# currentSense.net
KiCad netlist of a schematic drawn in Altium Designer
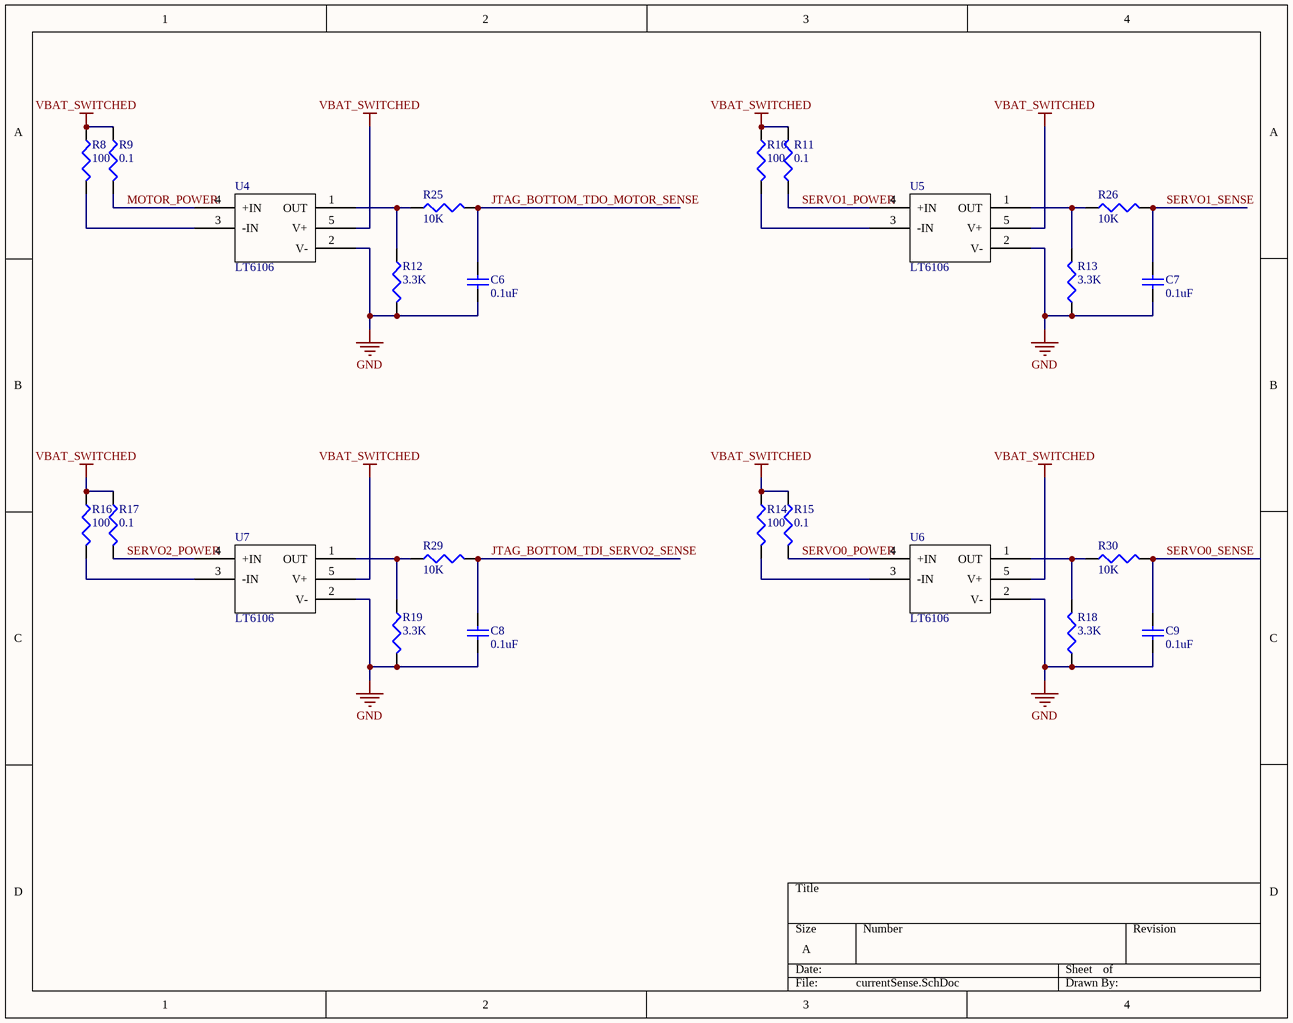
[diagram p0: currentSense.SchDoc]

(export (version "E")
  (design (tool "Eeschema 10.0.6"))
  (components
    (comp (ref "C6")
      (value "0.1uF")
      (footprint "CAPC1005L")
      (description "Capacitor (Semiconductor SIM Model)")
      (fields (field (name "Comment") "Cap Semi") (field (name "PUBLISHER") "Altium Limited"))
      (libsource (lib "Miscellaneous Devices") (part "Cap Semi"))
    )
    (comp (ref "C7")
      (value "0.1uF")
      (footprint "CAPC1005L")
      (description "Capacitor (Semiconductor SIM Model)")
      (fields (field (name "Comment") "Cap Semi") (field (name "PUBLISHER") "Altium Limited"))
      (libsource (lib "Miscellaneous Devices") (part "Cap Semi"))
    )
    (comp (ref "C8")
      (value "0.1uF")
      (footprint "CAPC1005L")
      (description "Capacitor (Semiconductor SIM Model)")
      (fields (field (name "Comment") "Cap Semi") (field (name "PUBLISHER") "Altium Limited"))
      (libsource (lib "Miscellaneous Devices") (part "Cap Semi"))
    )
    (comp (ref "C9")
      (value "0.1uF")
      (footprint "CAPC1005L")
      (description "Capacitor (Semiconductor SIM Model)")
      (fields (field (name "Comment") "Cap Semi") (field (name "PUBLISHER") "Altium Limited"))
      (libsource (lib "Miscellaneous Devices") (part "Cap Semi"))
    )
    (comp (ref "R8")
      (value "100")
      (footprint "J1-0603")
      (description "Resistor")
      (fields (field (name "Comment") "R_IN") (field (name "PUBLISHER") "Altium Limited"))
      (libsource (lib "Miscellaneous Devices") (part "Res3"))
    )
    (comp (ref "R9")
      (value "0.1")
      (footprint "J1-0603")
      (description "Resistor")
      (fields (field (name "Comment") "RLOAD") (field (name "PUBLISHER") "Altium Limited"))
      (libsource (lib "Miscellaneous Devices") (part "Res3"))
    )
    (comp (ref "R10")
      (value "100")
      (footprint "J1-0603")
      (description "Resistor")
      (fields (field (name "Comment") "R_IN") (field (name "PUBLISHER") "Altium Limited"))
      (libsource (lib "Miscellaneous Devices") (part "Res3"))
    )
    (comp (ref "R11")
      (value "0.1")
      (footprint "J1-0603")
      (description "Resistor")
      (fields (field (name "Comment") "RLOAD") (field (name "PUBLISHER") "Altium Limited"))
      (libsource (lib "Miscellaneous Devices") (part "Res3"))
    )
    (comp (ref "R12")
      (value "3.3K")
      (footprint "J1-0603")
      (description "Resistor")
      (fields (field (name "Comment") "R_OUT") (field (name "PUBLISHER") "Altium Limited"))
      (libsource (lib "Miscellaneous Devices") (part "Res3"))
    )
    (comp (ref "R13")
      (value "3.3K")
      (footprint "J1-0603")
      (description "Resistor")
      (fields (field (name "Comment") "R_OUT") (field (name "PUBLISHER") "Altium Limited"))
      (libsource (lib "Miscellaneous Devices") (part "Res3"))
    )
    (comp (ref "R14")
      (value "100")
      (footprint "J1-0603")
      (description "Resistor")
      (fields (field (name "Comment") "R_IN") (field (name "PUBLISHER") "Altium Limited"))
      (libsource (lib "Miscellaneous Devices") (part "Res3"))
    )
    (comp (ref "R15")
      (value "0.1")
      (footprint "J1-0603")
      (description "Resistor")
      (fields (field (name "Comment") "RLOAD") (field (name "PUBLISHER") "Altium Limited"))
      (libsource (lib "Miscellaneous Devices") (part "Res3"))
    )
    (comp (ref "R16")
      (value "100")
      (footprint "J1-0603")
      (description "Resistor")
      (fields (field (name "Comment") "R_IN") (field (name "PUBLISHER") "Altium Limited"))
      (libsource (lib "Miscellaneous Devices") (part "Res3"))
    )
    (comp (ref "R17")
      (value "0.1")
      (footprint "J1-0603")
      (description "Resistor")
      (fields (field (name "Comment") "RLOAD") (field (name "PUBLISHER") "Altium Limited"))
      (libsource (lib "Miscellaneous Devices") (part "Res3"))
    )
    (comp (ref "R18")
      (value "3.3K")
      (footprint "J1-0603")
      (description "Resistor")
      (fields (field (name "Comment") "R_OUT") (field (name "PUBLISHER") "Altium Limited"))
      (libsource (lib "Miscellaneous Devices") (part "Res3"))
    )
    (comp (ref "R19")
      (value "3.3K")
      (footprint "J1-0603")
      (description "Resistor")
      (fields (field (name "Comment") "R_OUT") (field (name "PUBLISHER") "Altium Limited"))
      (libsource (lib "Miscellaneous Devices") (part "Res3"))
    )
    (comp (ref "R25")
      (value "10K")
      (footprint "J1-0603")
      (description "Resistor")
      (fields (field (name "Comment") "LPF") (field (name "PUBLISHER") "Altium Limited"))
      (libsource (lib "Miscellaneous Devices") (part "Res3"))
    )
    (comp (ref "R26")
      (value "10K")
      (footprint "J1-0603")
      (description "Resistor")
      (fields (field (name "Comment") "LPF") (field (name "PUBLISHER") "Altium Limited"))
      (libsource (lib "Miscellaneous Devices") (part "Res3"))
    )
    (comp (ref "R29")
      (value "10K")
      (footprint "J1-0603")
      (description "Resistor")
      (fields (field (name "Comment") "LPF") (field (name "PUBLISHER") "Altium Limited"))
      (libsource (lib "Miscellaneous Devices") (part "Res3"))
    )
    (comp (ref "R30")
      (value "10K")
      (footprint "J1-0603")
      (description "Resistor")
      (fields (field (name "Comment") "LPF") (field (name "PUBLISHER") "Altium Limited"))
      (libsource (lib "Miscellaneous Devices") (part "Res3"))
    )
    (comp (ref "U4")
      (value "LT6106")
      (footprint "TSOT-23-5_LT6106")
      (description "Current Sense Amplifier")
      (libsource (lib "mrone") (part "LT6106"))
    )
    (comp (ref "U5")
      (value "LT6106")
      (footprint "TSOT-23-5_LT6106")
      (description "Current Sense Amplifier")
      (libsource (lib "mrone") (part "LT6106"))
    )
    (comp (ref "U6")
      (value "LT6106")
      (footprint "TSOT-23-5_LT6106")
      (description "Current Sense Amplifier")
      (libsource (lib "mrone") (part "LT6106"))
    )
    (comp (ref "U7")
      (value "LT6106")
      (footprint "TSOT-23-5_LT6106")
      (description "Current Sense Amplifier")
      (libsource (lib "mrone") (part "LT6106"))
    )
  )
  (nets
    (net (code "1") (name "/JTAG_BOTTOM_TDI_SERVO2_SENSE") (class "Default")
      (node (ref "C8") (pin "2") (pinfunction "2_2") (pintype "passive"))
      (node (ref "R29") (pin "2") (pinfunction "2_2") (pintype "passive"))
    )
    (net (code "2") (name "/JTAG_BOTTOM_TDO_MOTOR_SENSE") (class "Default")
      (node (ref "C6") (pin "2") (pinfunction "2_2") (pintype "passive"))
      (node (ref "R25") (pin "2") (pinfunction "2_2") (pintype "passive"))
    )
    (net (code "3") (name "/MOTOR_POWER") (class "Default")
      (node (ref "R9") (pin "2") (pinfunction "2_2") (pintype "passive"))
      (node (ref "U4") (pin "4") (pinfunction "+IN_4") (pintype "passive"))
    )
    (net (code "4") (name "/SERVO0_POWER") (class "Default")
      (node (ref "R15") (pin "2") (pinfunction "2_2") (pintype "passive"))
      (node (ref "U6") (pin "4") (pinfunction "+IN_4") (pintype "passive"))
    )
    (net (code "5") (name "/SERVO0_SENSE") (class "Default")
      (node (ref "C9") (pin "2") (pinfunction "2_2") (pintype "passive"))
      (node (ref "R30") (pin "2") (pinfunction "2_2") (pintype "passive"))
    )
    (net (code "6") (name "/SERVO1_POWER") (class "Default")
      (node (ref "R11") (pin "1") (pinfunction "1_1") (pintype "passive"))
      (node (ref "U5") (pin "4") (pinfunction "+IN_4") (pintype "passive"))
    )
    (net (code "7") (name "/SERVO1_SENSE") (class "Default")
      (node (ref "C7") (pin "2") (pinfunction "2_2") (pintype "passive"))
      (node (ref "R26") (pin "2") (pinfunction "2_2") (pintype "passive"))
    )
    (net (code "8") (name "/SERVO2_POWER") (class "Default")
      (node (ref "R17") (pin "2") (pinfunction "2_2") (pintype "passive"))
      (node (ref "U7") (pin "4") (pinfunction "+IN_4") (pintype "passive"))
    )
    (net (code "9") (name "GND") (class "Default")
      (node (ref "C6") (pin "1") (pinfunction "1_1") (pintype "passive"))
      (node (ref "C7") (pin "1") (pinfunction "1_1") (pintype "passive"))
      (node (ref "C8") (pin "1") (pinfunction "1_1") (pintype "passive"))
      (node (ref "C9") (pin "1") (pinfunction "1_1") (pintype "passive"))
      (node (ref "R12") (pin "2") (pinfunction "2_2") (pintype "passive"))
      (node (ref "R13") (pin "1") (pinfunction "1_1") (pintype "passive"))
      (node (ref "R18") (pin "1") (pinfunction "1_1") (pintype "passive"))
      (node (ref "R19") (pin "2") (pinfunction "2_2") (pintype "passive"))
      (node (ref "U4") (pin "2") (pinfunction "V-_2") (pintype "passive"))
      (node (ref "U5") (pin "2") (pinfunction "V-_2") (pintype "passive"))
      (node (ref "U6") (pin "2") (pinfunction "V-_2") (pintype "passive"))
      (node (ref "U7") (pin "2") (pinfunction "V-_2") (pintype "passive"))
    )
    (net (code "10") (name "Net-(U4--IN)") (class "Default")
      (node (ref "R8") (pin "2") (pinfunction "2_2") (pintype "passive"))
      (node (ref "U4") (pin "3") (pinfunction "-IN_3") (pintype "passive"))
    )
    (net (code "11") (name "Net-(U4-OUT)") (class "Default")
      (node (ref "R12") (pin "1") (pinfunction "1_1") (pintype "passive"))
      (node (ref "R25") (pin "1") (pinfunction "1_1") (pintype "passive"))
      (node (ref "U4") (pin "1") (pinfunction "OUT_1") (pintype "passive"))
    )
    (net (code "12") (name "Net-(U5--IN)") (class "Default")
      (node (ref "R10") (pin "2") (pinfunction "2_2") (pintype "passive"))
      (node (ref "U5") (pin "3") (pinfunction "-IN_3") (pintype "passive"))
    )
    (net (code "13") (name "Net-(U5-OUT)") (class "Default")
      (node (ref "R13") (pin "2") (pinfunction "2_2") (pintype "passive"))
      (node (ref "R26") (pin "1") (pinfunction "1_1") (pintype "passive"))
      (node (ref "U5") (pin "1") (pinfunction "OUT_1") (pintype "passive"))
    )
    (net (code "14") (name "Net-(U6--IN)") (class "Default")
      (node (ref "R14") (pin "2") (pinfunction "2_2") (pintype "passive"))
      (node (ref "U6") (pin "3") (pinfunction "-IN_3") (pintype "passive"))
    )
    (net (code "15") (name "Net-(U6-OUT)") (class "Default")
      (node (ref "R18") (pin "2") (pinfunction "2_2") (pintype "passive"))
      (node (ref "R30") (pin "1") (pinfunction "1_1") (pintype "passive"))
      (node (ref "U6") (pin "1") (pinfunction "OUT_1") (pintype "passive"))
    )
    (net (code "16") (name "Net-(U7--IN)") (class "Default")
      (node (ref "R16") (pin "2") (pinfunction "2_2") (pintype "passive"))
      (node (ref "U7") (pin "3") (pinfunction "-IN_3") (pintype "passive"))
    )
    (net (code "17") (name "Net-(U7-OUT)") (class "Default")
      (node (ref "R19") (pin "1") (pinfunction "1_1") (pintype "passive"))
      (node (ref "R29") (pin "1") (pinfunction "1_1") (pintype "passive"))
      (node (ref "U7") (pin "1") (pinfunction "OUT_1") (pintype "passive"))
    )
    (net (code "18") (name "VBAT_SWITCHED") (class "Default")
      (node (ref "R10") (pin "1") (pinfunction "1_1") (pintype "passive"))
      (node (ref "R11") (pin "2") (pinfunction "2_2") (pintype "passive"))
      (node (ref "R14") (pin "1") (pinfunction "1_1") (pintype "passive"))
      (node (ref "R15") (pin "1") (pinfunction "1_1") (pintype "passive"))
      (node (ref "R16") (pin "1") (pinfunction "1_1") (pintype "passive"))
      (node (ref "R17") (pin "1") (pinfunction "1_1") (pintype "passive"))
      (node (ref "R8") (pin "1") (pinfunction "1_1") (pintype "passive"))
      (node (ref "R9") (pin "1") (pinfunction "1_1") (pintype "passive"))
      (node (ref "U4") (pin "5") (pinfunction "V+_5") (pintype "passive"))
      (node (ref "U5") (pin "5") (pinfunction "V+_5") (pintype "passive"))
      (node (ref "U6") (pin "5") (pinfunction "V+_5") (pintype "passive"))
      (node (ref "U7") (pin "5") (pinfunction "V+_5") (pintype "passive"))
    )
  )
)
